# 201_ConnectionPart1-Part2.net
KiCad netlist of a schematic drawn in Altium Designer
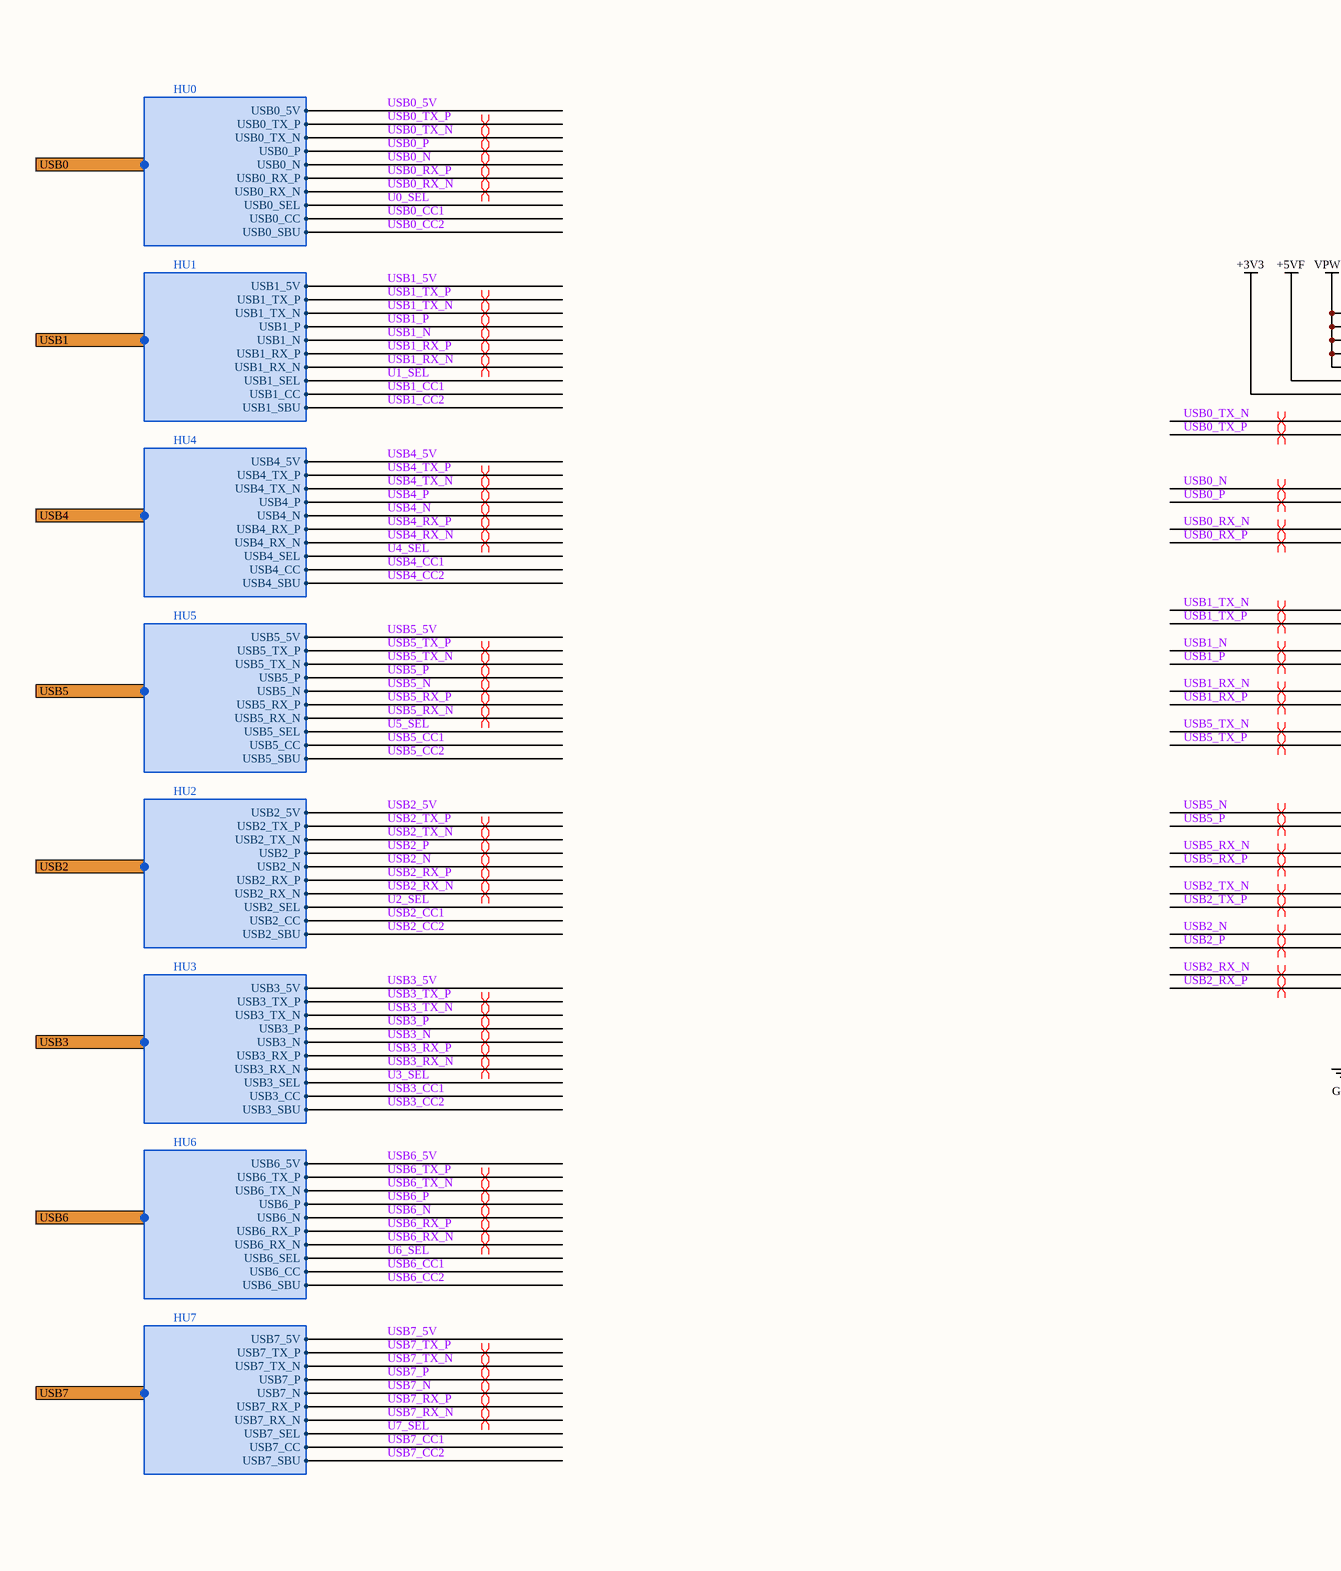
[diagram p0: 201_ConnectionPart1-Part2.SchDoc, left]
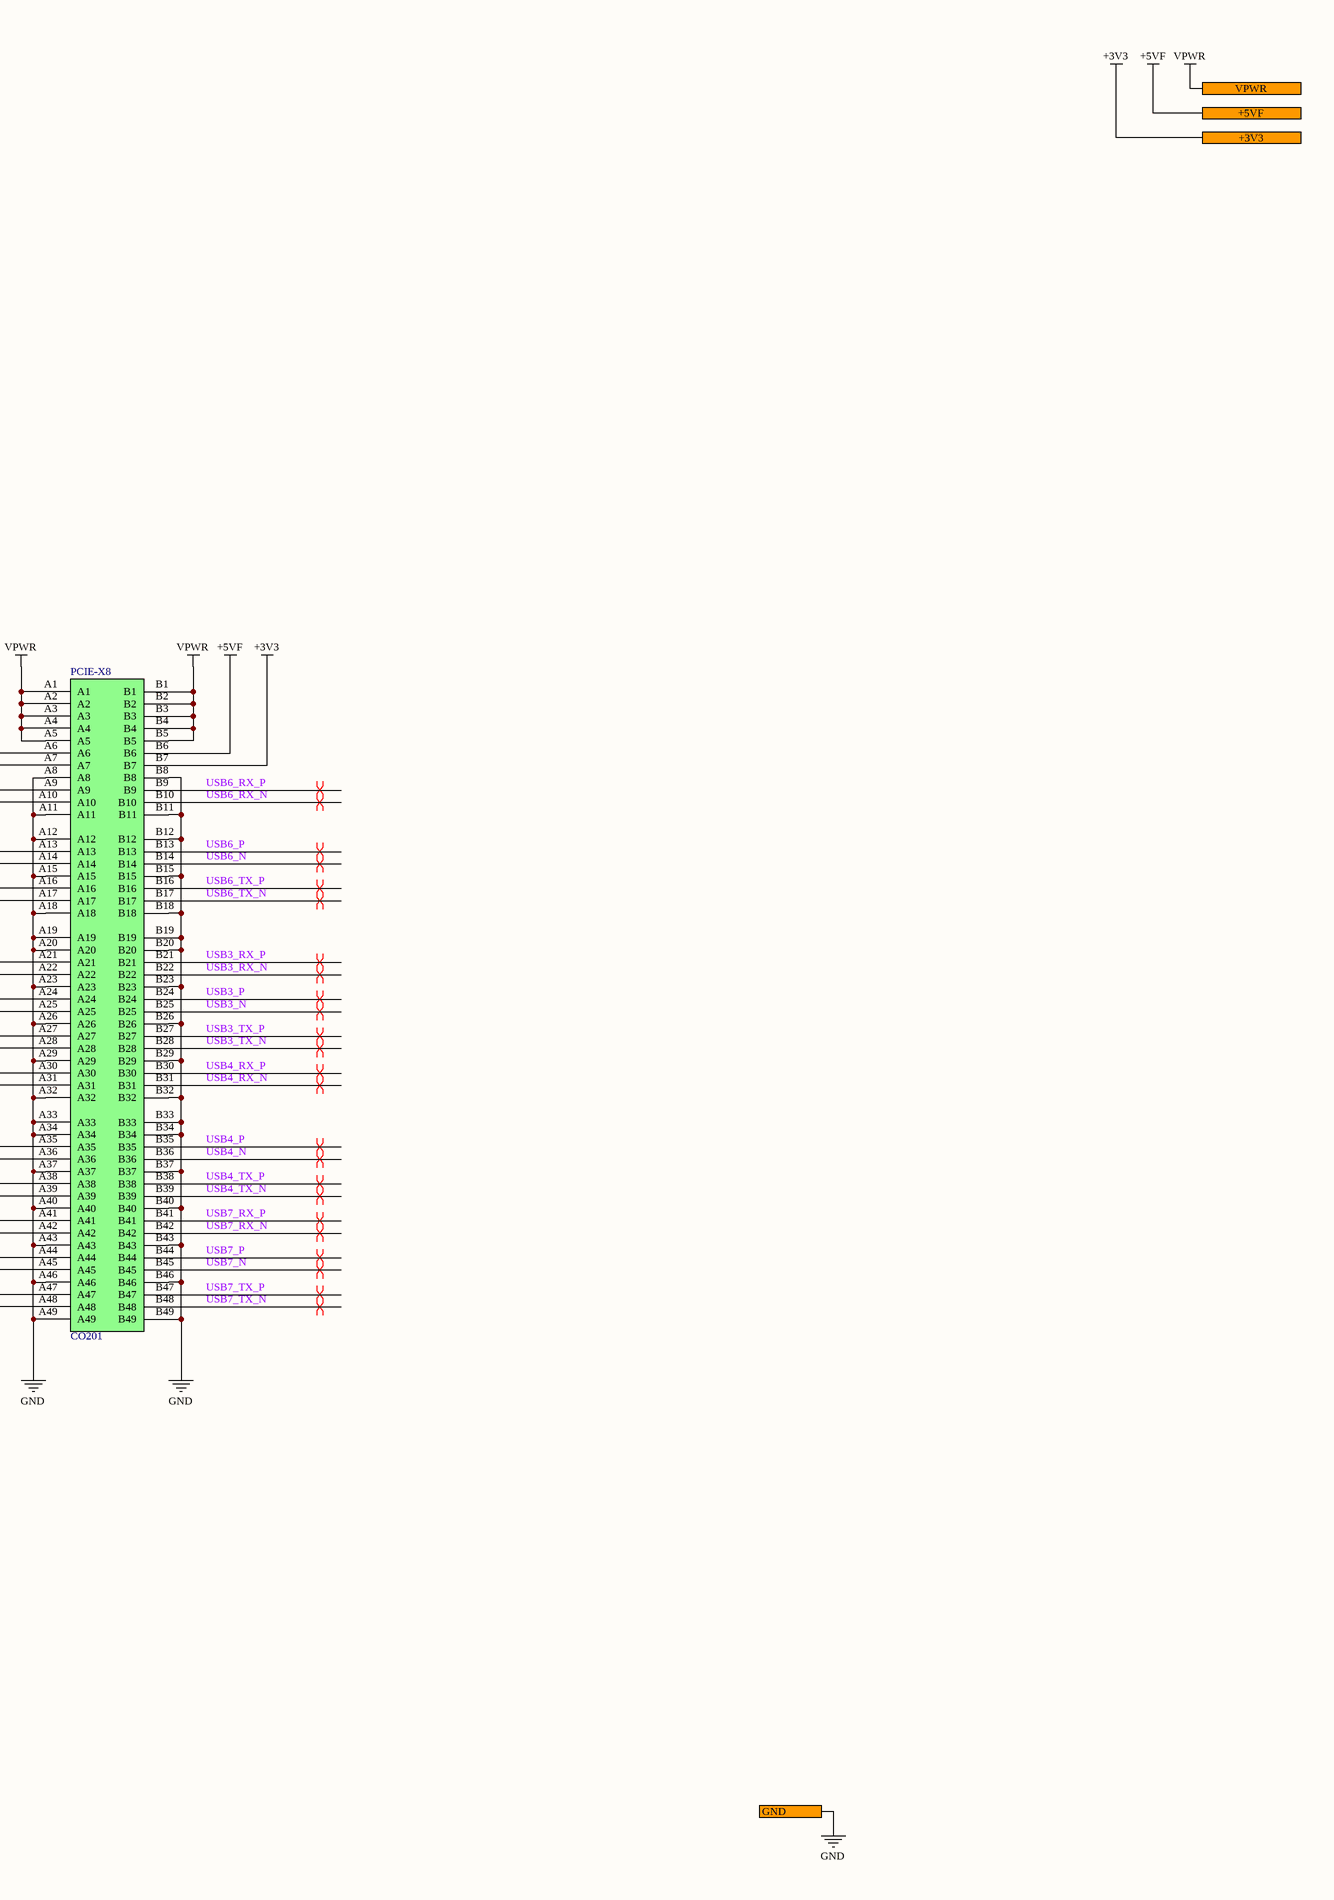
[diagram p1: 201_ConnectionPart1-Part2.SchDoc, right]

(export (version "E")
  (design (tool "Eeschema 10.0.6"))
  (components
    (comp (ref "CO201")
      (value "PCIE-X8")
      (footprint "1-2362375-3")
      (description "PCIE GEN4-X8, Female, Board guide, Locking ramp")
      (fields
        (field (name "REFVAL") "PCIE-X8")
        (field (name "PART NUMBER") "CO0048")
        (field (name "MANFACTPART") "1-2362375-3")
      )
      (libsource (lib "GTS_Database") (part "PCIE-X8"))
    )
  )
  (nets
    (net (code "9") (name "+3V3") (class "Default")
      (node (ref "CO201") (pin "A7") (pinfunction "A7_A7") (pintype "passive"))
      (node (ref "CO201") (pin "B7") (pinfunction "B7_B7") (pintype "passive"))
    )
    (net (code "10") (name "+5VF") (class "Default")
      (node (ref "CO201") (pin "A6") (pinfunction "A6_A6") (pintype "passive"))
      (node (ref "CO201") (pin "B6") (pinfunction "B6_B6") (pintype "passive"))
    )
    (net (code "22") (name "/USB0_N") (class "Default")
      (node (ref "CO201") (pin "A13") (pinfunction "A13_A13") (pintype "passive"))
    )
    (net (code "23") (name "/USB0_P") (class "Default")
      (node (ref "CO201") (pin "A14") (pinfunction "A14_A14") (pintype "passive"))
    )
    (net (code "24") (name "/USB0_RX_N") (class "Default")
      (node (ref "CO201") (pin "A16") (pinfunction "A16_A16") (pintype "passive"))
    )
    (net (code "25") (name "/USB0_RX_P") (class "Default")
      (node (ref "CO201") (pin "A17") (pinfunction "A17_A17") (pintype "passive"))
    )
    (net (code "26") (name "/USB0_TX_N") (class "Default")
      (node (ref "CO201") (pin "A9") (pinfunction "A9_A9") (pintype "passive"))
    )
    (net (code "27") (name "/USB0_TX_P") (class "Default")
      (node (ref "CO201") (pin "A10") (pinfunction "A10_A10") (pintype "passive"))
    )
    (net (code "31") (name "/USB1_N") (class "Default")
      (node (ref "CO201") (pin "A24") (pinfunction "A24_A24") (pintype "passive"))
    )
    (net (code "32") (name "/USB1_P") (class "Default")
      (node (ref "CO201") (pin "A25") (pinfunction "A25_A25") (pintype "passive"))
    )
    (net (code "33") (name "/USB1_RX_N") (class "Default")
      (node (ref "CO201") (pin "A27") (pinfunction "A27_A27") (pintype "passive"))
    )
    (net (code "34") (name "/USB1_RX_P") (class "Default")
      (node (ref "CO201") (pin "A28") (pinfunction "A28_A28") (pintype "passive"))
    )
    (net (code "35") (name "/USB1_TX_N") (class "Default")
      (node (ref "CO201") (pin "A21") (pinfunction "A21_A21") (pintype "passive"))
    )
    (net (code "36") (name "/USB1_TX_P") (class "Default")
      (node (ref "CO201") (pin "A22") (pinfunction "A22_A22") (pintype "passive"))
    )
    (net (code "40") (name "/USB2_N") (class "Default")
      (node (ref "CO201") (pin "A44") (pinfunction "A44_A44") (pintype "passive"))
    )
    (net (code "41") (name "/USB2_P") (class "Default")
      (node (ref "CO201") (pin "A45") (pinfunction "A45_A45") (pintype "passive"))
    )
    (net (code "42") (name "/USB2_RX_N") (class "Default")
      (node (ref "CO201") (pin "A47") (pinfunction "A47_A47") (pintype "passive"))
    )
    (net (code "43") (name "/USB2_RX_P") (class "Default")
      (node (ref "CO201") (pin "A48") (pinfunction "A48_A48") (pintype "passive"))
    )
    (net (code "44") (name "/USB2_TX_N") (class "Default")
      (node (ref "CO201") (pin "A41") (pinfunction "A41_A41") (pintype "passive"))
    )
    (net (code "45") (name "/USB2_TX_P") (class "Default")
      (node (ref "CO201") (pin "A42") (pinfunction "A42_A42") (pintype "passive"))
    )
    (net (code "49") (name "/USB3_N") (class "Default")
      (node (ref "CO201") (pin "B25") (pinfunction "B25_B25") (pintype "passive"))
    )
    (net (code "50") (name "/USB3_P") (class "Default")
      (node (ref "CO201") (pin "B24") (pinfunction "B24_B24") (pintype "passive"))
    )
    (net (code "51") (name "/USB3_RX_N") (class "Default")
      (node (ref "CO201") (pin "B22") (pinfunction "B22_B22") (pintype "passive"))
    )
    (net (code "52") (name "/USB3_RX_P") (class "Default")
      (node (ref "CO201") (pin "B21") (pinfunction "B21_B21") (pintype "passive"))
    )
    (net (code "53") (name "/USB3_TX_N") (class "Default")
      (node (ref "CO201") (pin "B28") (pinfunction "B28_B28") (pintype "passive"))
    )
    (net (code "54") (name "/USB3_TX_P") (class "Default")
      (node (ref "CO201") (pin "B27") (pinfunction "B27_B27") (pintype "passive"))
    )
    (net (code "58") (name "/USB4_N") (class "Default")
      (node (ref "CO201") (pin "B36") (pinfunction "B36_B36") (pintype "passive"))
    )
    (net (code "59") (name "/USB4_P") (class "Default")
      (node (ref "CO201") (pin "B35") (pinfunction "B35_B35") (pintype "passive"))
    )
    (net (code "60") (name "/USB4_RX_N") (class "Default")
      (node (ref "CO201") (pin "B31") (pinfunction "B31_B31") (pintype "passive"))
    )
    (net (code "61") (name "/USB4_RX_P") (class "Default")
      (node (ref "CO201") (pin "B30") (pinfunction "B30_B30") (pintype "passive"))
    )
    (net (code "62") (name "/USB4_TX_N") (class "Default")
      (node (ref "CO201") (pin "B39") (pinfunction "B39_B39") (pintype "passive"))
    )
    (net (code "63") (name "/USB4_TX_P") (class "Default")
      (node (ref "CO201") (pin "B38") (pinfunction "B38_B38") (pintype "passive"))
    )
    (net (code "67") (name "/USB5_N") (class "Default")
      (node (ref "CO201") (pin "A35") (pinfunction "A35_A35") (pintype "passive"))
    )
    (net (code "68") (name "/USB5_P") (class "Default")
      (node (ref "CO201") (pin "A36") (pinfunction "A36_A36") (pintype "passive"))
    )
    (net (code "69") (name "/USB5_RX_N") (class "Default")
      (node (ref "CO201") (pin "A38") (pinfunction "A38_A38") (pintype "passive"))
    )
    (net (code "70") (name "/USB5_RX_P") (class "Default")
      (node (ref "CO201") (pin "A39") (pinfunction "A39_A39") (pintype "passive"))
    )
    (net (code "71") (name "/USB5_TX_N") (class "Default")
      (node (ref "CO201") (pin "A30") (pinfunction "A30_A30") (pintype "passive"))
    )
    (net (code "72") (name "/USB5_TX_P") (class "Default")
      (node (ref "CO201") (pin "A31") (pinfunction "A31_A31") (pintype "passive"))
    )
    (net (code "76") (name "/USB6_N") (class "Default")
      (node (ref "CO201") (pin "B14") (pinfunction "B14_B14") (pintype "passive"))
    )
    (net (code "77") (name "/USB6_P") (class "Default")
      (node (ref "CO201") (pin "B13") (pinfunction "B13_B13") (pintype "passive"))
    )
    (net (code "78") (name "/USB6_RX_N") (class "Default")
      (node (ref "CO201") (pin "B10") (pinfunction "B10_B10") (pintype "passive"))
    )
    (net (code "79") (name "/USB6_RX_P") (class "Default")
      (node (ref "CO201") (pin "B9") (pinfunction "B9_B9") (pintype "passive"))
    )
    (net (code "80") (name "/USB6_TX_N") (class "Default")
      (node (ref "CO201") (pin "B17") (pinfunction "B17_B17") (pintype "passive"))
    )
    (net (code "81") (name "/USB6_TX_P") (class "Default")
      (node (ref "CO201") (pin "B16") (pinfunction "B16_B16") (pintype "passive"))
    )
    (net (code "85") (name "/USB7_N") (class "Default")
      (node (ref "CO201") (pin "B45") (pinfunction "B45_B45") (pintype "passive"))
    )
    (net (code "86") (name "/USB7_P") (class "Default")
      (node (ref "CO201") (pin "B44") (pinfunction "B44_B44") (pintype "passive"))
    )
    (net (code "87") (name "/USB7_RX_N") (class "Default")
      (node (ref "CO201") (pin "B42") (pinfunction "B42_B42") (pintype "passive"))
    )
    (net (code "88") (name "/USB7_RX_P") (class "Default")
      (node (ref "CO201") (pin "B41") (pinfunction "B41_B41") (pintype "passive"))
    )
    (net (code "89") (name "/USB7_TX_N") (class "Default")
      (node (ref "CO201") (pin "B48") (pinfunction "B48_B48") (pintype "passive"))
    )
    (net (code "90") (name "/USB7_TX_P") (class "Default")
      (node (ref "CO201") (pin "B47") (pinfunction "B47_B47") (pintype "passive"))
    )
    (net (code "99") (name "GND") (class "Default")
      (node (ref "CO201") (pin "A11") (pinfunction "A11_A11") (pintype "passive"))
      (node (ref "CO201") (pin "A12") (pinfunction "A12_A12") (pintype "passive"))
      (node (ref "CO201") (pin "A15") (pinfunction "A15_A15") (pintype "passive"))
      (node (ref "CO201") (pin "A18") (pinfunction "A18_A18") (pintype "passive"))
      (node (ref "CO201") (pin "A19") (pinfunction "A19_A19") (pintype "passive"))
      (node (ref "CO201") (pin "A20") (pinfunction "A20_A20") (pintype "passive"))
      (node (ref "CO201") (pin "A23") (pinfunction "A23_A23") (pintype "passive"))
      (node (ref "CO201") (pin "A26") (pinfunction "A26_A26") (pintype "passive"))
      (node (ref "CO201") (pin "A29") (pinfunction "A29_A29") (pintype "passive"))
      (node (ref "CO201") (pin "A32") (pinfunction "A32_A32") (pintype "passive"))
      (node (ref "CO201") (pin "A33") (pinfunction "A33_A33") (pintype "passive"))
      (node (ref "CO201") (pin "A34") (pinfunction "A34_A34") (pintype "passive"))
      (node (ref "CO201") (pin "A37") (pinfunction "A37_A37") (pintype "passive"))
      (node (ref "CO201") (pin "A40") (pinfunction "A40_A40") (pintype "passive"))
      (node (ref "CO201") (pin "A43") (pinfunction "A43_A43") (pintype "passive"))
      (node (ref "CO201") (pin "A46") (pinfunction "A46_A46") (pintype "passive"))
      (node (ref "CO201") (pin "A49") (pinfunction "A49_A49") (pintype "passive"))
      (node (ref "CO201") (pin "A8") (pinfunction "A8_A8") (pintype "passive"))
      (node (ref "CO201") (pin "B11") (pinfunction "B11_B11") (pintype "passive"))
      (node (ref "CO201") (pin "B12") (pinfunction "B12_B12") (pintype "passive"))
      (node (ref "CO201") (pin "B15") (pinfunction "B15_B15") (pintype "passive"))
      (node (ref "CO201") (pin "B18") (pinfunction "B18_B18") (pintype "passive"))
      (node (ref "CO201") (pin "B19") (pinfunction "B19_B19") (pintype "passive"))
      (node (ref "CO201") (pin "B20") (pinfunction "B20_B20") (pintype "passive"))
      (node (ref "CO201") (pin "B23") (pinfunction "B23_B23") (pintype "passive"))
      (node (ref "CO201") (pin "B26") (pinfunction "B26_B26") (pintype "passive"))
      (node (ref "CO201") (pin "B29") (pinfunction "B29_B29") (pintype "passive"))
      (node (ref "CO201") (pin "B32") (pinfunction "B32_B32") (pintype "passive"))
      (node (ref "CO201") (pin "B33") (pinfunction "B33_B33") (pintype "passive"))
      (node (ref "CO201") (pin "B34") (pinfunction "B34_B34") (pintype "passive"))
      (node (ref "CO201") (pin "B37") (pinfunction "B37_B37") (pintype "passive"))
      (node (ref "CO201") (pin "B40") (pinfunction "B40_B40") (pintype "passive"))
      (node (ref "CO201") (pin "B43") (pinfunction "B43_B43") (pintype "passive"))
      (node (ref "CO201") (pin "B46") (pinfunction "B46_B46") (pintype "passive"))
      (node (ref "CO201") (pin "B49") (pinfunction "B49_B49") (pintype "passive"))
      (node (ref "CO201") (pin "B8") (pinfunction "B8_B8") (pintype "passive"))
    )
    (net (code "100") (name "VPWR") (class "Default")
      (node (ref "CO201") (pin "A1") (pinfunction "A1_A1") (pintype "passive"))
      (node (ref "CO201") (pin "A2") (pinfunction "A2_A2") (pintype "passive"))
      (node (ref "CO201") (pin "A3") (pinfunction "A3_A3") (pintype "passive"))
      (node (ref "CO201") (pin "A4") (pinfunction "A4_A4") (pintype "passive"))
      (node (ref "CO201") (pin "A5") (pinfunction "A5_A5") (pintype "passive"))
      (node (ref "CO201") (pin "B1") (pinfunction "B1_B1") (pintype "passive"))
      (node (ref "CO201") (pin "B2") (pinfunction "B2_B2") (pintype "passive"))
      (node (ref "CO201") (pin "B3") (pinfunction "B3_B3") (pintype "passive"))
      (node (ref "CO201") (pin "B4") (pinfunction "B4_B4") (pintype "passive"))
      (node (ref "CO201") (pin "B5") (pinfunction "B5_B5") (pintype "passive"))
    )
  )
)
